# Minimal_ATTINY85.net
KiCad netlist of a schematic drawn in EAGLE
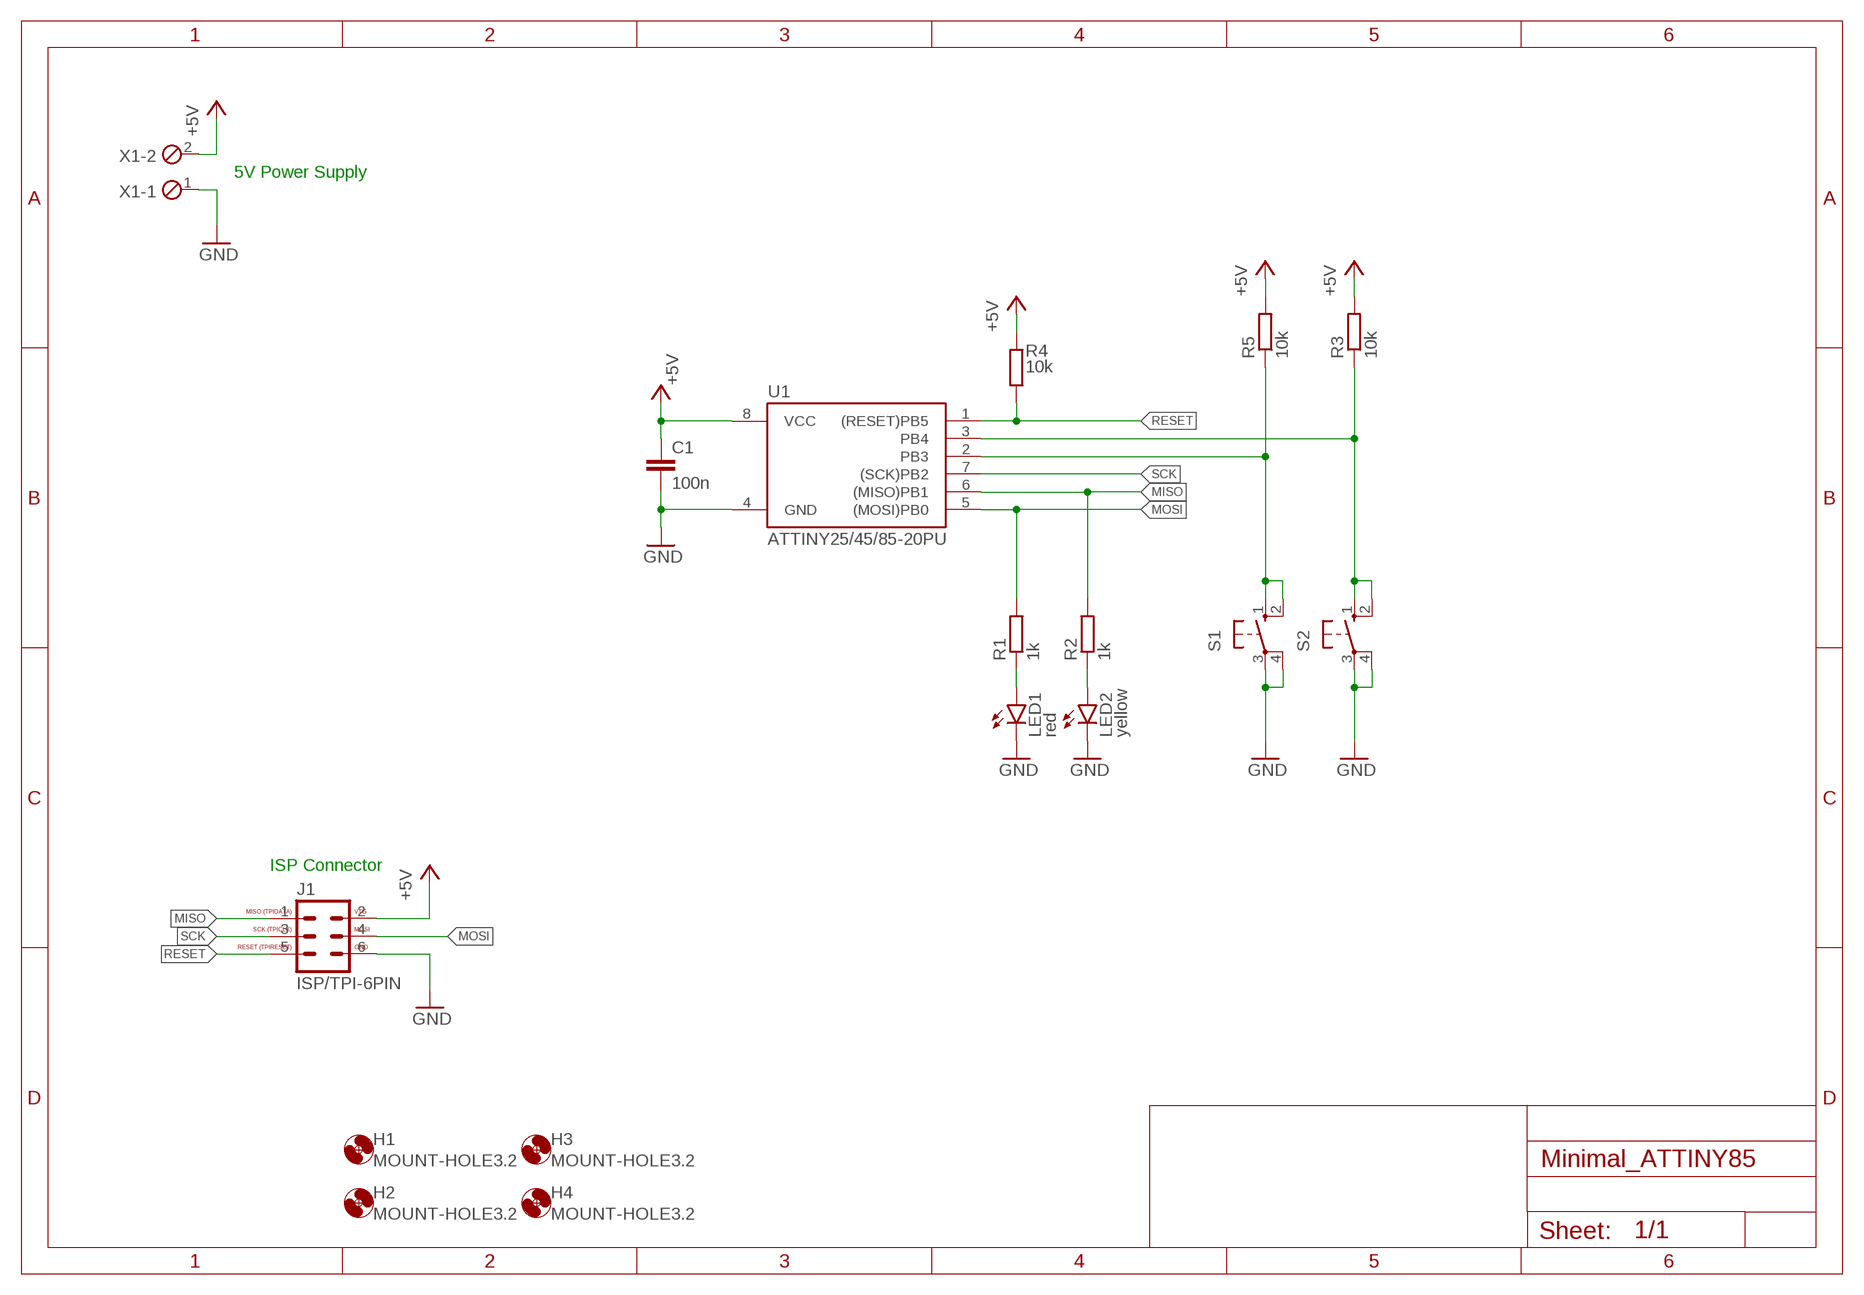
[diagram p0: schematic, sheet 1]

(export (version "E")
  (design (tool "Eeschema 10.0.6"))
  (components
    (comp (ref "C1")
      (value "100n")
      (footprint "eagle-import:C050-024X044")
      (libsource (lib "eagle-import") (part "C-EU050-024X044"))
    )
    (comp (ref "H1")
      (value "MOUNT-HOLE3.2")
      (footprint "eagle-import:3,2")
      (libsource (lib "eagle-import") (part "MOUNT-HOLE3.2"))
    )
    (comp (ref "H2")
      (value "MOUNT-HOLE3.2")
      (footprint "eagle-import:3,2")
      (libsource (lib "eagle-import") (part "MOUNT-HOLE3.2"))
    )
    (comp (ref "H3")
      (value "MOUNT-HOLE3.2")
      (footprint "eagle-import:3,2")
      (libsource (lib "eagle-import") (part "MOUNT-HOLE3.2"))
    )
    (comp (ref "H4")
      (value "MOUNT-HOLE3.2")
      (footprint "eagle-import:3,2")
      (libsource (lib "eagle-import") (part "MOUNT-HOLE3.2"))
    )
    (comp (ref "J1")
      (value "ISP/TPI-6PIN")
      (footprint "eagle-import:ML6")
      (libsource (lib "eagle-import") (part "ISP/TPI-6PIN"))
    )
    (comp (ref "LED1")
      (value "red")
      (footprint "eagle-import:LED5MM")
      (libsource (lib "eagle-import") (part "LED5MM"))
    )
    (comp (ref "LED2")
      (value "yellow")
      (footprint "eagle-import:LED5MM")
      (libsource (lib "eagle-import") (part "LED5MM"))
    )
    (comp (ref "R1")
      (value "1k")
      (footprint "eagle-import:0207_5V")
      (libsource (lib "eagle-import") (part "R-EU_0207/5V"))
    )
    (comp (ref "R2")
      (value "1k")
      (footprint "eagle-import:0207_5V")
      (libsource (lib "eagle-import") (part "R-EU_0207/5V"))
    )
    (comp (ref "R3")
      (value "10k")
      (footprint "eagle-import:0207_5V")
      (libsource (lib "eagle-import") (part "R-EU_0207/5V"))
    )
    (comp (ref "R4")
      (value "10k")
      (footprint "eagle-import:0207_5V")
      (libsource (lib "eagle-import") (part "R-EU_0207/5V"))
    )
    (comp (ref "R5")
      (value "10k")
      (footprint "eagle-import:0207_5V")
      (libsource (lib "eagle-import") (part "R-EU_0207/5V"))
    )
    (comp (ref "S1")
      (value "10-XX")
      (footprint "eagle-import:B3F-10XX")
      (fields (field (name "MPN") "B3F-1000"))
      (libsource (lib "eagle-import") (part "10-XX"))
    )
    (comp (ref "S2")
      (value "10-XX")
      (footprint "eagle-import:B3F-10XX")
      (fields (field (name "MPN") "B3F-1000"))
      (libsource (lib "eagle-import") (part "10-XX"))
    )
    (comp (ref "U1")
      (value "ATTINY25/45/85-20PU")
      (footprint "eagle-import:DIL08")
      (libsource (lib "eagle-import") (part "ATTINY25/45/85-20PU"))
    )
    (comp (ref "X1")
      (value "MPT2")
      (footprint "eagle-import:2POL254")
      (libsource (lib "eagle-import") (part "MPT2"))
    )
  )
  (nets
    (net (code "1") (name "+5V") (class "Default")
      (node (ref "C1") (pin "1") (pinfunction "1_1") (pintype "passive"))
      (node (ref "J1") (pin "2") (pinfunction "2_2") (pintype "passive"))
      (node (ref "R3") (pin "2") (pinfunction "2_2") (pintype "passive"))
      (node (ref "R4") (pin "1") (pinfunction "1_1") (pintype "passive"))
      (node (ref "R5") (pin "2") (pinfunction "2_2") (pintype "passive"))
      (node (ref "U1") (pin "8") (pinfunction "VCC_8") (pintype "power_in"))
      (node (ref "X1") (pin "2") (pinfunction "1_2") (pintype "passive"))
    )
    (net (code "2") (name "GND") (class "Default")
      (node (ref "C1") (pin "2") (pinfunction "2_2") (pintype "passive"))
      (node (ref "J1") (pin "6") (pinfunction "6_6") (pintype "passive"))
      (node (ref "LED1") (pin "K") (pinfunction "C_K") (pintype "passive"))
      (node (ref "LED2") (pin "K") (pinfunction "C_K") (pintype "passive"))
      (node (ref "S1") (pin "3") (pinfunction "P_3") (pintype "passive"))
      (node (ref "S1") (pin "4") (pinfunction "P1_4") (pintype "passive"))
      (node (ref "S2") (pin "3") (pinfunction "P_3") (pintype "passive"))
      (node (ref "S2") (pin "4") (pinfunction "P1_4") (pintype "passive"))
      (node (ref "U1") (pin "4") (pinfunction "GND_4") (pintype "power_in"))
      (node (ref "X1") (pin "1") (pinfunction "1_1") (pintype "passive"))
    )
    (net (code "3") (name "MISO") (class "Default")
      (node (ref "J1") (pin "1") (pinfunction "1_1") (pintype "passive"))
      (node (ref "R2") (pin "2") (pinfunction "2_2") (pintype "passive"))
      (node (ref "U1") (pin "6") (pinfunction "(MISO)PB1_6") (pintype "bidirectional"))
    )
    (net (code "4") (name "MOSI") (class "Default")
      (node (ref "J1") (pin "4") (pinfunction "4_4") (pintype "passive"))
      (node (ref "R1") (pin "2") (pinfunction "2_2") (pintype "passive"))
      (node (ref "U1") (pin "5") (pinfunction "(MOSI)PB0_5") (pintype "bidirectional"))
    )
    (net (code "5") (name "Net-(LED1-PadA)") (class "Default")
      (node (ref "LED1") (pin "A") (pinfunction "A_A") (pintype "passive"))
      (node (ref "R1") (pin "1") (pinfunction "1_1") (pintype "passive"))
    )
    (net (code "6") (name "Net-(LED2-PadA)") (class "Default")
      (node (ref "LED2") (pin "A") (pinfunction "A_A") (pintype "passive"))
      (node (ref "R2") (pin "1") (pinfunction "1_1") (pintype "passive"))
    )
    (net (code "7") (name "Net-(S1-S)") (class "Default")
      (node (ref "R5") (pin "1") (pinfunction "1_1") (pintype "passive"))
      (node (ref "S1") (pin "1") (pinfunction "S_1") (pintype "passive"))
      (node (ref "S1") (pin "2") (pinfunction "S1_2") (pintype "passive"))
      (node (ref "U1") (pin "2") (pinfunction "PB3_2") (pintype "bidirectional"))
    )
    (net (code "8") (name "Net-(S2-S)") (class "Default")
      (node (ref "R3") (pin "1") (pinfunction "1_1") (pintype "passive"))
      (node (ref "S2") (pin "1") (pinfunction "S_1") (pintype "passive"))
      (node (ref "S2") (pin "2") (pinfunction "S1_2") (pintype "passive"))
      (node (ref "U1") (pin "3") (pinfunction "PB4_3") (pintype "bidirectional"))
    )
    (net (code "9") (name "RESET") (class "Default")
      (node (ref "J1") (pin "5") (pinfunction "5_5") (pintype "passive"))
      (node (ref "R4") (pin "2") (pinfunction "2_2") (pintype "passive"))
      (node (ref "U1") (pin "1") (pinfunction "(RESET)PB5_1") (pintype "bidirectional"))
    )
    (net (code "10") (name "SCK") (class "Default")
      (node (ref "J1") (pin "3") (pinfunction "3_3") (pintype "passive"))
      (node (ref "U1") (pin "7") (pinfunction "(SCK)PB2_7") (pintype "bidirectional"))
    )
  )
)
